# acdr_3_1.net
KiCad netlist of a schematic drawn in EAGLE
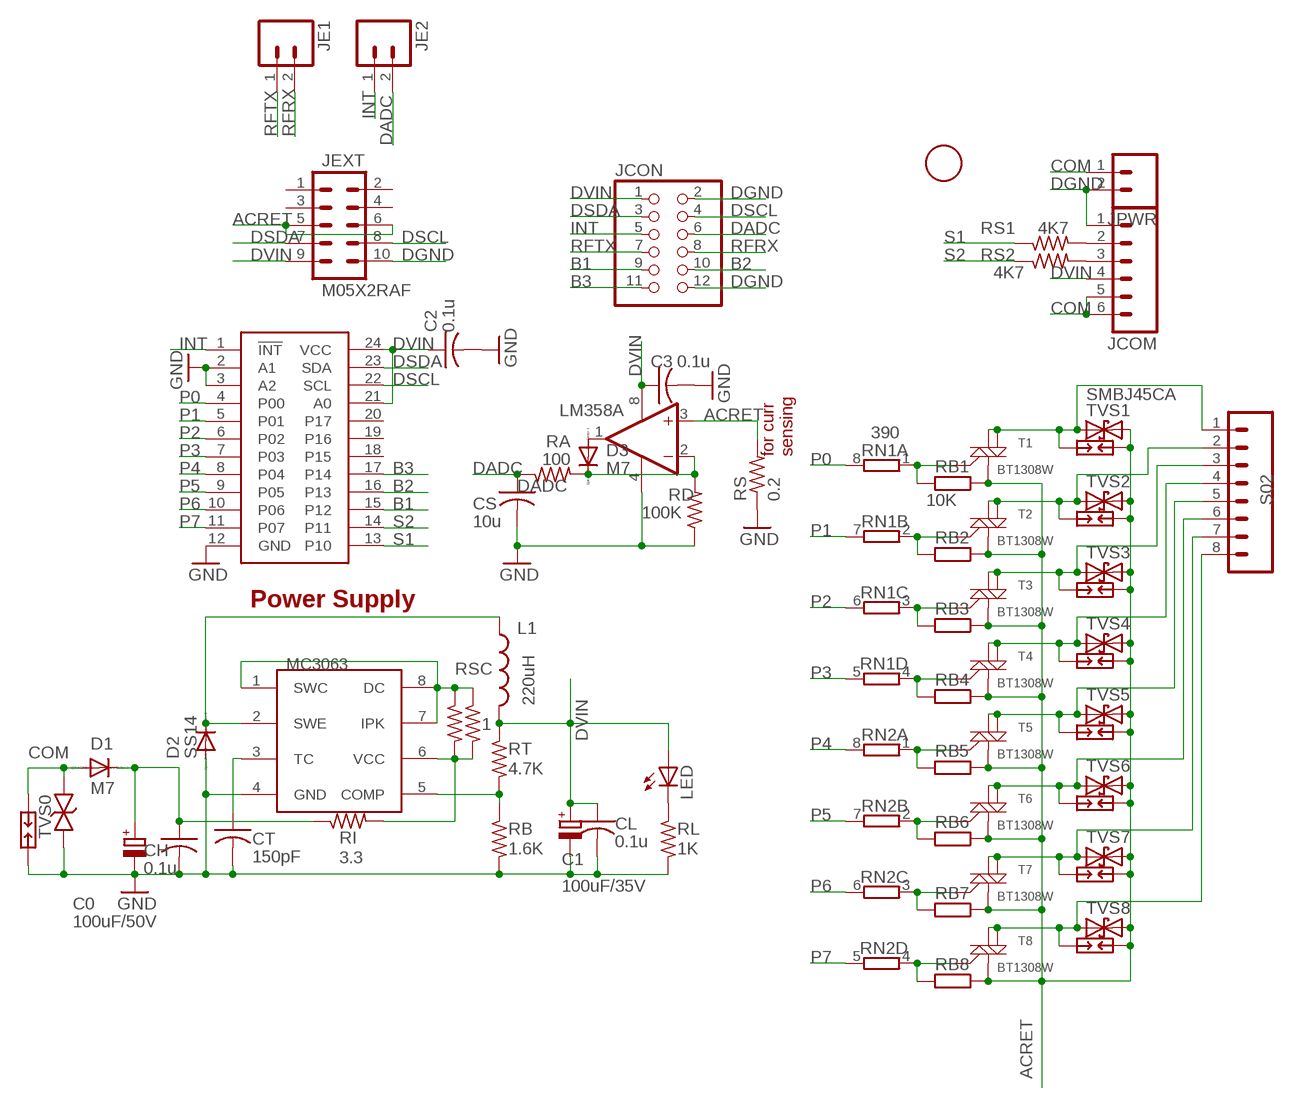
[diagram p0: schematic, sheet 1]

(export (version "E")
  (design (tool "Eeschema 10.0.6"))
  (components
    (comp (ref "1F")
      (value "FIDUCIAL")
      (footprint "eagle-import:FIDUCIAL_1MM")
      (libsource (lib "eagle-import") (part "FIDUCIAL"))
    )
    (comp (ref "C0")
      (value "100uF/50V")
      (footprint "eagle-import:PANASONIC_E")
      (libsource (lib "eagle-import") (part "CPOL-EUE"))
    )
    (comp (ref "C1")
      (value "100uF/35V")
      (footprint "eagle-import:PANASONIC_D")
      (libsource (lib "eagle-import") (part "CPOL-EUD"))
    )
    (comp (ref "C2")
      (value "0.1u")
      (footprint "eagle-import:C0603")
      (libsource (lib "eagle-import") (part "C-USC0603"))
    )
    (comp (ref "C3")
      (value "0.1u")
      (footprint "eagle-import:C0603")
      (libsource (lib "eagle-import") (part "C-USC0603"))
    )
    (comp (ref "CH")
      (value "0.1u")
      (footprint "eagle-import:C0603")
      (libsource (lib "eagle-import") (part "C-USC0603"))
    )
    (comp (ref "CL")
      (value "0.1u")
      (footprint "eagle-import:C0603")
      (libsource (lib "eagle-import") (part "C-USC0603"))
    )
    (comp (ref "CS")
      (value "10u")
      (footprint "eagle-import:C0805K")
      (libsource (lib "eagle-import") (part "C-USC0805K"))
    )
    (comp (ref "CT")
      (value "150pF")
      (footprint "eagle-import:C0603K")
      (libsource (lib "eagle-import") (part "C-USC0603K"))
    )
    (comp (ref "D1")
      (value "M7")
      (footprint "eagle-import:DO-214AC")
      (libsource (lib "eagle-import") (part "DIODE-DO-214AC"))
    )
    (comp (ref "D2")
      (value "SS14")
      (footprint "eagle-import:DO-214AC")
      (libsource (lib "eagle-import") (part "DIODE-DO-214AC"))
    )
    (comp (ref "D3")
      (value "M7")
      (footprint "eagle-import:DO-214AC")
      (libsource (lib "eagle-import") (part "DIODE-DO-214AC"))
    )
    (comp (ref "JCOM")
      (value "M065MM")
      (footprint "eagle-import:SCREWTERMINAL-5MM-6")
      (libsource (lib "eagle-import") (part "M065MM"))
    )
    (comp (ref "JCON")
      (value "PINHD-2X6")
      (footprint "eagle-import:2X06")
      (libsource (lib "eagle-import") (part "PINHD-2X6"))
    )
    (comp (ref "JE1")
      (value "M02PTH")
      (footprint "eagle-import:1X02")
      (libsource (lib "eagle-import") (part "SparkFunNew_M02PTH"))
    )
    (comp (ref "JE2")
      (value "M02PTH")
      (footprint "eagle-import:1X02")
      (libsource (lib "eagle-import") (part "SparkFunNew_M02PTH"))
    )
    (comp (ref "JEXT")
      (value "M05X2RAF")
      (footprint "eagle-import:2X5-RAF")
      (libsource (lib "eagle-import") (part "M05X2RAF"))
    )
    (comp (ref "JPWR")
      (value "M024MM-X")
      (footprint "eagle-import:SCREWTERMINAL-4MM-2-X")
      (libsource (lib "eagle-import") (part "M024MM-X"))
    )
    (comp (ref "L1")
      (value "220uH")
      (footprint "eagle-import:SRU1038")
      (libsource (lib "eagle-import") (part "INDUCTORSRU1038"))
    )
    (comp (ref "LED")
      (value "LEDCHIPLED_0805")
      (footprint "eagle-import:CHIPLED_0805")
      (libsource (lib "eagle-import") (part "LEDCHIPLED_0805"))
    )
    (comp (ref "LM358")
      (value "OP262D")
      (footprint "eagle-import:SO08")
      (libsource (lib "eagle-import") (part "OP262D"))
    )
    (comp (ref "MC3063")
      (value "MC34063")
      (footprint "eagle-import:SO08")
      (libsource (lib "eagle-import") (part "MC33063/MC34063D"))
    )
    (comp (ref "PCA9555")
      (value "PCA9555")
      (footprint "eagle-import:TSSOP24")
      (libsource (lib "eagle-import") (part "PCF8575TSSOP24"))
    )
    (comp (ref "RA")
      (value "100")
      (footprint "eagle-import:R0603")
      (libsource (lib "eagle-import") (part "R-US_R0603"))
    )
    (comp (ref "RB")
      (value "1.6K")
      (footprint "eagle-import:R0603")
      (libsource (lib "eagle-import") (part "adafruitGood_R-US_R0603"))
    )
    (comp (ref "RB1")
      (value "10K")
      (footprint "eagle-import:R0603")
      (libsource (lib "eagle-import") (part "R-EU_R0603"))
    )
    (comp (ref "RB2")
      (value "10K")
      (footprint "eagle-import:R0603")
      (libsource (lib "eagle-import") (part "R-EU_R0603"))
    )
    (comp (ref "RB3")
      (value "10K")
      (footprint "eagle-import:R0603")
      (libsource (lib "eagle-import") (part "R-EU_R0603"))
    )
    (comp (ref "RB4")
      (value "10K")
      (footprint "eagle-import:R0603")
      (libsource (lib "eagle-import") (part "R-EU_R0603"))
    )
    (comp (ref "RB5")
      (value "10K")
      (footprint "eagle-import:R0603")
      (libsource (lib "eagle-import") (part "R-EU_R0603"))
    )
    (comp (ref "RB6")
      (value "10K")
      (footprint "eagle-import:R0603")
      (libsource (lib "eagle-import") (part "R-EU_R0603"))
    )
    (comp (ref "RB7")
      (value "10K")
      (footprint "eagle-import:R0603")
      (libsource (lib "eagle-import") (part "R-EU_R0603"))
    )
    (comp (ref "RB8")
      (value "10K")
      (footprint "eagle-import:R0603")
      (libsource (lib "eagle-import") (part "R-EU_R0603"))
    )
    (comp (ref "RD")
      (value "100K")
      (footprint "eagle-import:R0603")
      (libsource (lib "eagle-import") (part "R-US_R0603"))
    )
    (comp (ref "RI")
      (value "3.3")
      (footprint "eagle-import:R2010")
      (libsource (lib "eagle-import") (part "adafruitGood_R-US_R2010"))
    )
    (comp (ref "RL")
      (value "1K")
      (footprint "eagle-import:R0603")
      (libsource (lib "eagle-import") (part "R-US_R0603"))
    )
    (comp (ref "RN1")
      (value "390")
      (footprint "eagle-import:EXB38V")
      (libsource (lib "eagle-import") (part "4R-NEXB38V"))
    )
    (comp (ref "RN2")
      (value "390")
      (footprint "eagle-import:EXB38V")
      (libsource (lib "eagle-import") (part "4R-NEXB38V"))
    )
    (comp (ref "RS")
      (value "0.2")
      (footprint "eagle-import:R2512")
      (libsource (lib "eagle-import") (part "R-US_R2512"))
    )
    (comp (ref "RS1")
      (value "4K7")
      (footprint "eagle-import:R0603")
      (libsource (lib "eagle-import") (part "R-US_R0603"))
    )
    (comp (ref "RS2")
      (value "4K7")
      (footprint "eagle-import:R0603")
      (libsource (lib "eagle-import") (part "R-US_R0603"))
    )
    (comp (ref "RSC")
      (value "1")
      (footprint "eagle-import:R0805")
      (libsource (lib "eagle-import") (part "adafruitGood_R-US_R0805"))
    )
    (comp (ref "RSC1")
      (value "1")
      (footprint "eagle-import:R0805")
      (libsource (lib "eagle-import") (part "adafruitGood_R-US_R0805"))
    )
    (comp (ref "RT")
      (value "4.7K")
      (footprint "eagle-import:R0603")
      (libsource (lib "eagle-import") (part "adafruitGood_R-US_R0603"))
    )
    (comp (ref "S02")
      (value "M085MM-8")
      (footprint "eagle-import:SCREWTERMINAL-5MM-8")
      (libsource (lib "eagle-import") (part "M085MM-8"))
    )
    (comp (ref "SP0")
      (value "PCB-SGAP")
      (footprint "eagle-import:PCB-SGAP")
      (libsource (lib "eagle-import") (part "PCB-SGAP"))
    )
    (comp (ref "SP1")
      (value "PCB-SGAP")
      (footprint "eagle-import:PCB-SGAP")
      (libsource (lib "eagle-import") (part "PCB-SGAP"))
    )
    (comp (ref "SP2")
      (value "PCB-SGAP")
      (footprint "eagle-import:PCB-SGAP")
      (libsource (lib "eagle-import") (part "PCB-SGAP"))
    )
    (comp (ref "SP3")
      (value "PCB-SGAP")
      (footprint "eagle-import:PCB-SGAP")
      (libsource (lib "eagle-import") (part "PCB-SGAP"))
    )
    (comp (ref "SP4")
      (value "PCB-SGAP")
      (footprint "eagle-import:PCB-SGAP")
      (libsource (lib "eagle-import") (part "PCB-SGAP"))
    )
    (comp (ref "SP5")
      (value "PCB-SGAP")
      (footprint "eagle-import:PCB-SGAP")
      (libsource (lib "eagle-import") (part "PCB-SGAP"))
    )
    (comp (ref "SP6")
      (value "PCB-SGAP")
      (footprint "eagle-import:PCB-SGAP")
      (libsource (lib "eagle-import") (part "PCB-SGAP"))
    )
    (comp (ref "SP7")
      (value "PCB-SGAP")
      (footprint "eagle-import:PCB-SGAP")
      (libsource (lib "eagle-import") (part "PCB-SGAP"))
    )
    (comp (ref "SP8")
      (value "PCB-SGAP")
      (footprint "eagle-import:PCB-SGAP")
      (libsource (lib "eagle-import") (part "PCB-SGAP"))
    )
    (comp (ref "T1")
      (value "BT1308W")
      (footprint "eagle-import:SOT223")
      (libsource (lib "eagle-import") (part "MAC97SOT223"))
    )
    (comp (ref "T2")
      (value "BT1308W")
      (footprint "eagle-import:SOT223")
      (libsource (lib "eagle-import") (part "MAC97SOT223"))
    )
    (comp (ref "T3")
      (value "BT1308W")
      (footprint "eagle-import:SOT223")
      (libsource (lib "eagle-import") (part "MAC97SOT223"))
    )
    (comp (ref "T4")
      (value "BT1308W")
      (footprint "eagle-import:SOT223")
      (libsource (lib "eagle-import") (part "MAC97SOT223"))
    )
    (comp (ref "T5")
      (value "BT1308W")
      (footprint "eagle-import:SOT223")
      (libsource (lib "eagle-import") (part "MAC97SOT223"))
    )
    (comp (ref "T6")
      (value "BT1308W")
      (footprint "eagle-import:SOT223")
      (libsource (lib "eagle-import") (part "MAC97SOT223"))
    )
    (comp (ref "T7")
      (value "BT1308W")
      (footprint "eagle-import:SOT223")
      (libsource (lib "eagle-import") (part "MAC97SOT223"))
    )
    (comp (ref "T8")
      (value "BT1308W")
      (footprint "eagle-import:SOT223")
      (libsource (lib "eagle-import") (part "MAC97SOT223"))
    )
    (comp (ref "TVS0")
      (value "SMBJ45CA")
      (footprint "eagle-import:SMB")
      (libsource (lib "eagle-import") (part "DIODE-BTVSSMB"))
    )
    (comp (ref "TVS1")
      (value "SMBJ45CA")
      (footprint "eagle-import:SMB")
      (libsource (lib "eagle-import") (part "TVSSMB"))
    )
    (comp (ref "TVS2")
      (value "SMBJ45CA")
      (footprint "eagle-import:SMB")
      (libsource (lib "eagle-import") (part "TVSSMB"))
    )
    (comp (ref "TVS3")
      (value "SMBJ45CA")
      (footprint "eagle-import:SMB")
      (libsource (lib "eagle-import") (part "TVSSMB"))
    )
    (comp (ref "TVS4")
      (value "SMBJ45CA")
      (footprint "eagle-import:SMB")
      (libsource (lib "eagle-import") (part "TVSSMB"))
    )
    (comp (ref "TVS5")
      (value "SMBJ45CA")
      (footprint "eagle-import:SMB")
      (libsource (lib "eagle-import") (part "TVSSMB"))
    )
    (comp (ref "TVS6")
      (value "SMBJ45CA")
      (footprint "eagle-import:SMB")
      (libsource (lib "eagle-import") (part "TVSSMB"))
    )
    (comp (ref "TVS7")
      (value "SMBJ45CA")
      (footprint "eagle-import:SMB")
      (libsource (lib "eagle-import") (part "TVSSMB"))
    )
    (comp (ref "TVS8")
      (value "SMBJ45CA")
      (footprint "eagle-import:SMB")
      (libsource (lib "eagle-import") (part "TVSSMB"))
    )
  )
  (nets
    (net (code "1") (name "/ACRET") (class "Default")
      (node (ref "JEXT") (pin "5") (pinfunction "5_5") (pintype "passive"))
      (node (ref "JEXT") (pin "6") (pinfunction "6_6") (pintype "passive"))
      (node (ref "LM358") (pin "3") (pinfunction "+IN_3") (pintype "input"))
      (node (ref "RB1") (pin "1") (pinfunction "1_1") (pintype "passive"))
      (node (ref "RB2") (pin "1") (pinfunction "1_1") (pintype "passive"))
      (node (ref "RB3") (pin "1") (pinfunction "1_1") (pintype "passive"))
      (node (ref "RB4") (pin "1") (pinfunction "1_1") (pintype "passive"))
      (node (ref "RB5") (pin "1") (pinfunction "1_1") (pintype "passive"))
      (node (ref "RB6") (pin "1") (pinfunction "1_1") (pintype "passive"))
      (node (ref "RB7") (pin "1") (pinfunction "1_1") (pintype "passive"))
      (node (ref "RB8") (pin "1") (pinfunction "1_1") (pintype "passive"))
      (node (ref "RS") (pin "2") (pinfunction "2_2") (pintype "passive"))
      (node (ref "SP1") (pin "1") (pinfunction "1_1") (pintype "passive"))
      (node (ref "SP2") (pin "1") (pinfunction "1_1") (pintype "passive"))
      (node (ref "SP3") (pin "1") (pinfunction "1_1") (pintype "passive"))
      (node (ref "SP4") (pin "1") (pinfunction "1_1") (pintype "passive"))
      (node (ref "SP5") (pin "1") (pinfunction "1_1") (pintype "passive"))
      (node (ref "SP6") (pin "1") (pinfunction "1_1") (pintype "passive"))
      (node (ref "SP7") (pin "1") (pinfunction "1_1") (pintype "passive"))
      (node (ref "SP8") (pin "1") (pinfunction "1_1") (pintype "passive"))
      (node (ref "T1") (pin "1") (pinfunction "M1_1") (pintype "bidirectional"))
      (node (ref "T2") (pin "1") (pinfunction "M1_1") (pintype "bidirectional"))
      (node (ref "T3") (pin "1") (pinfunction "M1_1") (pintype "bidirectional"))
      (node (ref "T4") (pin "1") (pinfunction "M1_1") (pintype "bidirectional"))
      (node (ref "T5") (pin "1") (pinfunction "M1_1") (pintype "bidirectional"))
      (node (ref "T6") (pin "1") (pinfunction "M1_1") (pintype "bidirectional"))
      (node (ref "T7") (pin "1") (pinfunction "M1_1") (pintype "bidirectional"))
      (node (ref "T8") (pin "1") (pinfunction "M1_1") (pintype "bidirectional"))
      (node (ref "TVS1") (pin "C") (pinfunction "C_C") (pintype "passive"))
      (node (ref "TVS2") (pin "C") (pinfunction "C_C") (pintype "passive"))
      (node (ref "TVS3") (pin "C") (pinfunction "C_C") (pintype "passive"))
      (node (ref "TVS4") (pin "C") (pinfunction "C_C") (pintype "passive"))
      (node (ref "TVS5") (pin "C") (pinfunction "C_C") (pintype "passive"))
      (node (ref "TVS6") (pin "C") (pinfunction "C_C") (pintype "passive"))
      (node (ref "TVS7") (pin "C") (pinfunction "C_C") (pintype "passive"))
      (node (ref "TVS8") (pin "C") (pinfunction "C_C") (pintype "passive"))
    )
    (net (code "2") (name "/B1") (class "Default")
      (node (ref "JCON") (pin "9") (pinfunction "9_9") (pintype "passive"))
      (node (ref "PCA9555") (pin "15") (pinfunction "P12_15") (pintype "bidirectional"))
    )
    (net (code "3") (name "/B2") (class "Default")
      (node (ref "JCON") (pin "10") (pinfunction "10_10") (pintype "passive"))
      (node (ref "PCA9555") (pin "16") (pinfunction "P13_16") (pintype "bidirectional"))
    )
    (net (code "4") (name "/B3") (class "Default")
      (node (ref "JCON") (pin "11") (pinfunction "11_11") (pintype "passive"))
      (node (ref "PCA9555") (pin "17") (pinfunction "P14_17") (pintype "bidirectional"))
    )
    (net (code "5") (name "/COM") (class "Default")
      (node (ref "D1") (pin "A") (pinfunction "A_A") (pintype "passive"))
      (node (ref "JCOM") (pin "5") (pinfunction "5_5") (pintype "passive"))
      (node (ref "JCOM") (pin "6") (pinfunction "6_6") (pintype "passive"))
      (node (ref "JPWR") (pin "1") (pinfunction "1_1") (pintype "passive"))
      (node (ref "SP0") (pin "1") (pinfunction "1_1") (pintype "passive"))
      (node (ref "TVS0") (pin "C") (pinfunction "C_C") (pintype "passive"))
    )
    (net (code "6") (name "/DADC") (class "Default")
      (node (ref "CS") (pin "1") (pinfunction "1_1") (pintype "passive"))
      (node (ref "JCON") (pin "6") (pinfunction "6_6") (pintype "passive"))
      (node (ref "JE2") (pin "2") (pinfunction "2_2") (pintype "passive"))
      (node (ref "RA") (pin "1") (pinfunction "1_1") (pintype "passive"))
    )
    (net (code "7") (name "/DSCL") (class "Default")
      (node (ref "JCON") (pin "4") (pinfunction "4_4") (pintype "passive"))
      (node (ref "JEXT") (pin "8") (pinfunction "8_8") (pintype "passive"))
      (node (ref "PCA9555") (pin "22") (pinfunction "SCL_22") (pintype "bidirectional"))
    )
    (net (code "8") (name "/DSDA") (class "Default")
      (node (ref "JCON") (pin "3") (pinfunction "3_3") (pintype "passive"))
      (node (ref "JEXT") (pin "7") (pinfunction "7_7") (pintype "passive"))
      (node (ref "PCA9555") (pin "23") (pinfunction "SDA_23") (pintype "bidirectional"))
    )
    (net (code "9") (name "/DVIN") (class "Default")
      (node (ref "C1") (pin "+") (pinfunction "+_+") (pintype "passive"))
      (node (ref "C2") (pin "1") (pinfunction "1_1") (pintype "passive"))
      (node (ref "C3") (pin "1") (pinfunction "1_1") (pintype "passive"))
      (node (ref "CL") (pin "1") (pinfunction "1_1") (pintype "passive"))
      (node (ref "JCOM") (pin "4") (pinfunction "4_4") (pintype "passive"))
      (node (ref "JCON") (pin "1") (pinfunction "1_1") (pintype "passive"))
      (node (ref "JEXT") (pin "9") (pinfunction "9_9") (pintype "passive"))
      (node (ref "L1") (pin "2") (pinfunction "2_2") (pintype "passive"))
      (node (ref "LED") (pin "A") (pinfunction "A_A") (pintype "passive"))
      (node (ref "LM358") (pin "8") (pinfunction "V+_8") (pintype "power_in"))
      (node (ref "PCA9555") (pin "21") (pinfunction "A0_21") (pintype "bidirectional"))
      (node (ref "PCA9555") (pin "24") (pinfunction "VCC_24") (pintype "power_in"))
      (node (ref "RT") (pin "1") (pinfunction "1_1") (pintype "passive"))
    )
    (net (code "10") (name "/INT") (class "Default")
      (node (ref "JCON") (pin "5") (pinfunction "5_5") (pintype "passive"))
      (node (ref "JE2") (pin "1") (pinfunction "1_1") (pintype "passive"))
      (node (ref "PCA9555") (pin "1") (pinfunction "~{INT}_1") (pintype "bidirectional"))
    )
    (net (code "11") (name "/P0") (class "Default")
      (node (ref "PCA9555") (pin "4") (pinfunction "P00_4") (pintype "bidirectional"))
      (node (ref "RN1") (pin "8") (pinfunction "2_8") (pintype "passive"))
    )
    (net (code "12") (name "/P1") (class "Default")
      (node (ref "PCA9555") (pin "5") (pinfunction "P01_5") (pintype "bidirectional"))
      (node (ref "RN1") (pin "7") (pinfunction "2_7") (pintype "passive"))
    )
    (net (code "13") (name "/P2") (class "Default")
      (node (ref "PCA9555") (pin "6") (pinfunction "P02_6") (pintype "bidirectional"))
      (node (ref "RN1") (pin "6") (pinfunction "2_6") (pintype "passive"))
    )
    (net (code "14") (name "/P3") (class "Default")
      (node (ref "PCA9555") (pin "7") (pinfunction "P03_7") (pintype "bidirectional"))
      (node (ref "RN1") (pin "5") (pinfunction "2_5") (pintype "passive"))
    )
    (net (code "15") (name "/P4") (class "Default")
      (node (ref "PCA9555") (pin "8") (pinfunction "P04_8") (pintype "bidirectional"))
      (node (ref "RN2") (pin "8") (pinfunction "2_8") (pintype "passive"))
    )
    (net (code "16") (name "/P5") (class "Default")
      (node (ref "PCA9555") (pin "9") (pinfunction "P05_9") (pintype "bidirectional"))
      (node (ref "RN2") (pin "7") (pinfunction "2_7") (pintype "passive"))
    )
    (net (code "17") (name "/P6") (class "Default")
      (node (ref "PCA9555") (pin "10") (pinfunction "P06_10") (pintype "bidirectional"))
      (node (ref "RN2") (pin "6") (pinfunction "2_6") (pintype "passive"))
    )
    (net (code "18") (name "/P7") (class "Default")
      (node (ref "PCA9555") (pin "11") (pinfunction "P07_11") (pintype "bidirectional"))
      (node (ref "RN2") (pin "5") (pinfunction "2_5") (pintype "passive"))
    )
    (net (code "19") (name "/RFRX") (class "Default")
      (node (ref "JCON") (pin "8") (pinfunction "8_8") (pintype "passive"))
      (node (ref "JE1") (pin "2") (pinfunction "2_2") (pintype "passive"))
    )
    (net (code "20") (name "/RFTX") (class "Default")
      (node (ref "JCON") (pin "7") (pinfunction "7_7") (pintype "passive"))
      (node (ref "JE1") (pin "1") (pinfunction "1_1") (pintype "passive"))
    )
    (net (code "21") (name "/S1") (class "Default")
      (node (ref "PCA9555") (pin "13") (pinfunction "P10_13") (pintype "bidirectional"))
      (node (ref "RS1") (pin "1") (pinfunction "1_1") (pintype "passive"))
    )
    (net (code "22") (name "/S2") (class "Default")
      (node (ref "PCA9555") (pin "14") (pinfunction "P11_14") (pintype "bidirectional"))
      (node (ref "RS2") (pin "1") (pinfunction "1_1") (pintype "passive"))
    )
    (net (code "23") (name "GND") (class "Default")
      (node (ref "C0") (pin "-") (pinfunction "-_-") (pintype "passive"))
      (node (ref "C1") (pin "-") (pinfunction "-_-") (pintype "passive"))
      (node (ref "C2") (pin "2") (pinfunction "2_2") (pintype "passive"))
      (node (ref "C3") (pin "2") (pinfunction "2_2") (pintype "passive"))
      (node (ref "CH") (pin "2") (pinfunction "2_2") (pintype "passive"))
      (node (ref "CL") (pin "2") (pinfunction "2_2") (pintype "passive"))
      (node (ref "CS") (pin "2") (pinfunction "2_2") (pintype "passive"))
      (node (ref "CT") (pin "2") (pinfunction "2_2") (pintype "passive"))
      (node (ref "D2") (pin "A") (pinfunction "A_A") (pintype "passive"))
      (node (ref "JCOM") (pin "1") (pinfunction "1_1") (pintype "passive"))
      (node (ref "JCON") (pin "12") (pinfunction "12_12") (pintype "passive"))
      (node (ref "JCON") (pin "2") (pinfunction "2_2") (pintype "passive"))
      (node (ref "JEXT") (pin "10") (pinfunction "10_10") (pintype "passive"))
      (node (ref "JPWR") (pin "2") (pinfunction "2_2") (pintype "passive"))
      (node (ref "LM358") (pin "4") (pinfunction "V-_4") (pintype "power_in"))
      (node (ref "MC3063") (pin "4") (pinfunction "GND_4") (pintype "power_in"))
      (node (ref "PCA9555") (pin "12") (pinfunction "GND_12") (pintype "power_in"))
      (node (ref "PCA9555") (pin "2") (pinfunction "A1_2") (pintype "bidirectional"))
      (node (ref "PCA9555") (pin "3") (pinfunction "A2_3") (pintype "bidirectional"))
      (node (ref "RB") (pin "2") (pinfunction "2_2") (pintype "passive"))
      (node (ref "RD") (pin "1") (pinfunction "1_1") (pintype "passive"))
      (node (ref "RL") (pin "2") (pinfunction "2_2") (pintype "passive"))
      (node (ref "RS") (pin "1") (pinfunction "1_1") (pintype "passive"))
      (node (ref "SP0") (pin "2") (pinfunction "2_2") (pintype "passive"))
      (node (ref "TVS0") (pin "A") (pinfunction "A_A") (pintype "passive"))
    )
    (net (code "24") (name "Net-(C0-Pad+)") (class "Default")
      (node (ref "C0") (pin "+") (pinfunction "+_+") (pintype "passive"))
      (node (ref "CH") (pin "1") (pinfunction "1_1") (pintype "passive"))
      (node (ref "D1") (pin "C") (pinfunction "C_C") (pintype "passive"))
      (node (ref "RI") (pin "1") (pinfunction "1_1") (pintype "passive"))
    )
    (net (code "25") (name "Net-(JCOM-Pad2)") (class "Default")
      (node (ref "JCOM") (pin "2") (pinfunction "2_2") (pintype "passive"))
      (node (ref "RS1") (pin "2") (pinfunction "2_2") (pintype "passive"))
    )
    (net (code "26") (name "Net-(JCOM-Pad3)") (class "Default")
      (node (ref "JCOM") (pin "3") (pinfunction "3_3") (pintype "passive"))
      (node (ref "RS2") (pin "2") (pinfunction "2_2") (pintype "passive"))
    )
    (net (code "27") (name "Net-(LED-PadC)") (class "Default")
      (node (ref "LED") (pin "C") (pinfunction "C_C") (pintype "passive"))
      (node (ref "RL") (pin "1") (pinfunction "1_1") (pintype "passive"))
    )
    (net (code "28") (name "Net-(LM358A--IN)") (class "Default")
      (node (ref "D3") (pin "C") (pinfunction "C_C") (pintype "passive"))
      (node (ref "LM358") (pin "2") (pinfunction "-IN_2") (pintype "input"))
      (node (ref "RA") (pin "2") (pinfunction "2_2") (pintype "passive"))
      (node (ref "RD") (pin "2") (pinfunction "2_2") (pintype "passive"))
    )
    (net (code "29") (name "Net-(LM358A-OUT)") (class "Default")
      (node (ref "D3") (pin "A") (pinfunction "A_A") (pintype "passive"))
      (node (ref "LM358") (pin "1") (pinfunction "OUT_1") (pintype "output"))
    )
    (net (code "30") (name "Net-(MC3063-COMP)") (class "Default")
      (node (ref "MC3063") (pin "5") (pinfunction "COMP_5") (pintype "input"))
      (node (ref "RB") (pin "1") (pinfunction "1_1") (pintype "passive"))
      (node (ref "RT") (pin "2") (pinfunction "2_2") (pintype "passive"))
    )
    (net (code "31") (name "Net-(MC3063-DC)") (class "Default")
      (node (ref "MC3063") (pin "1") (pinfunction "SWC_1") (pintype "input"))
      (node (ref "MC3063") (pin "7") (pinfunction "IPK_7") (pintype "bidirectional"))
      (node (ref "MC3063") (pin "8") (pinfunction "DC_8") (pintype "input"))
      (node (ref "RSC") (pin "1") (pinfunction "1_1") (pintype "passive"))
      (node (ref "RSC1") (pin "1") (pinfunction "1_1") (pintype "passive"))
    )
    (net (code "32") (name "Net-(MC3063-SWE)") (class "Default")
      (node (ref "D2") (pin "C") (pinfunction "C_C") (pintype "passive"))
      (node (ref "L1") (pin "1") (pinfunction "1_1") (pintype "passive"))
      (node (ref "MC3063") (pin "2") (pinfunction "SWE_2") (pintype "input"))
    )
    (net (code "33") (name "Net-(MC3063-TC)") (class "Default")
      (node (ref "CT") (pin "1") (pinfunction "1_1") (pintype "passive"))
      (node (ref "MC3063") (pin "3") (pinfunction "TC_3") (pintype "input"))
    )
    (net (code "34") (name "Net-(MC3063-VCC)") (class "Default")
      (node (ref "MC3063") (pin "6") (pinfunction "VCC_6") (pintype "power_in"))
      (node (ref "RI") (pin "2") (pinfunction "2_2") (pintype "passive"))
      (node (ref "RSC") (pin "2") (pinfunction "2_2") (pintype "passive"))
      (node (ref "RSC1") (pin "2") (pinfunction "2_2") (pintype "passive"))
    )
    (net (code "35") (name "Net-(RN1B-1)") (class "Default")
      (node (ref "RB2") (pin "2") (pinfunction "2_2") (pintype "passive"))
      (node (ref "RN1") (pin "2") (pinfunction "1_2") (pintype "passive"))
      (node (ref "T2") (pin "3") (pinfunction "G_3") (pintype "bidirectional"))
    )
    (net (code "36") (name "Net-(RN1C-1)") (class "Default")
      (node (ref "RB3") (pin "2") (pinfunction "2_2") (pintype "passive"))
      (node (ref "RN1") (pin "3") (pinfunction "1_3") (pintype "passive"))
      (node (ref "T3") (pin "3") (pinfunction "G_3") (pintype "bidirectional"))
    )
    (net (code "37") (name "Net-(RN1D-1)") (class "Default")
      (node (ref "RB4") (pin "2") (pinfunction "2_2") (pintype "passive"))
      (node (ref "RN1") (pin "4") (pinfunction "1_4") (pintype "passive"))
      (node (ref "T4") (pin "3") (pinfunction "G_3") (pintype "bidirectional"))
    )
    (net (code "38") (name "Net-(RN2B-1)") (class "Default")
      (node (ref "RB6") (pin "2") (pinfunction "2_2") (pintype "passive"))
      (node (ref "RN2") (pin "2") (pinfunction "1_2") (pintype "passive"))
      (node (ref "T6") (pin "3") (pinfunction "G_3") (pintype "bidirectional"))
    )
    (net (code "39") (name "Net-(RN2C-1)") (class "Default")
      (node (ref "RB7") (pin "2") (pinfunction "2_2") (pintype "passive"))
      (node (ref "RN2") (pin "3") (pinfunction "1_3") (pintype "passive"))
      (node (ref "T7") (pin "3") (pinfunction "G_3") (pintype "bidirectional"))
    )
    (net (code "40") (name "Net-(RN2D-1)") (class "Default")
      (node (ref "RB8") (pin "2") (pinfunction "2_2") (pintype "passive"))
      (node (ref "RN2") (pin "4") (pinfunction "1_4") (pintype "passive"))
      (node (ref "T8") (pin "3") (pinfunction "G_3") (pintype "bidirectional"))
    )
    (net (code "41") (name "Net-(T1-G)") (class "Default")
      (node (ref "RB1") (pin "2") (pinfunction "2_2") (pintype "passive"))
      (node (ref "RN1") (pin "1") (pinfunction "1_1") (pintype "passive"))
      (node (ref "T1") (pin "3") (pinfunction "G_3") (pintype "bidirectional"))
    )
    (net (code "42") (name "Net-(T1-M2)") (class "Default")
      (node (ref "S02") (pin "1") (pinfunction "1_1") (pintype "passive"))
      (node (ref "SP1") (pin "2") (pinfunction "2_2") (pintype "passive"))
      (node (ref "T1") (pin "2") (pinfunction "M2_2") (pintype "bidirectional"))
      (node (ref "T1") (pin "4") (pinfunction "M2-4_4") (pintype "bidirectional"))
      (node (ref "TVS1") (pin "A") (pinfunction "A_A") (pintype "passive"))
    )
    (net (code "43") (name "Net-(T2-M2)") (class "Default")
      (node (ref "S02") (pin "2") (pinfunction "2_2") (pintype "passive"))
      (node (ref "SP2") (pin "2") (pinfunction "2_2") (pintype "passive"))
      (node (ref "T2") (pin "2") (pinfunction "M2_2") (pintype "bidirectional"))
      (node (ref "T2") (pin "4") (pinfunction "M2-4_4") (pintype "bidirectional"))
      (node (ref "TVS2") (pin "A") (pinfunction "A_A") (pintype "passive"))
    )
    (net (code "44") (name "Net-(T3-M2)") (class "Default")
      (node (ref "S02") (pin "3") (pinfunction "3_3") (pintype "passive"))
      (node (ref "SP3") (pin "2") (pinfunction "2_2") (pintype "passive"))
      (node (ref "T3") (pin "2") (pinfunction "M2_2") (pintype "bidirectional"))
      (node (ref "T3") (pin "4") (pinfunction "M2-4_4") (pintype "bidirectional"))
      (node (ref "TVS3") (pin "A") (pinfunction "A_A") (pintype "passive"))
    )
    (net (code "45") (name "Net-(T4-M2)") (class "Default")
      (node (ref "S02") (pin "4") (pinfunction "4_4") (pintype "passive"))
      (node (ref "SP4") (pin "2") (pinfunction "2_2") (pintype "passive"))
      (node (ref "T4") (pin "2") (pinfunction "M2_2") (pintype "bidirectional"))
      (node (ref "T4") (pin "4") (pinfunction "M2-4_4") (pintype "bidirectional"))
      (node (ref "TVS4") (pin "A") (pinfunction "A_A") (pintype "passive"))
    )
    (net (code "46") (name "Net-(T5-G)") (class "Default")
      (node (ref "RB5") (pin "2") (pinfunction "2_2") (pintype "passive"))
      (node (ref "RN2") (pin "1") (pinfunction "1_1") (pintype "passive"))
      (node (ref "T5") (pin "3") (pinfunction "G_3") (pintype "bidirectional"))
    )
    (net (code "47") (name "Net-(T5-M2)") (class "Default")
      (node (ref "S02") (pin "5") (pinfunction "5_5") (pintype "passive"))
      (node (ref "SP5") (pin "2") (pinfunction "2_2") (pintype "passive"))
      (node (ref "T5") (pin "2") (pinfunction "M2_2") (pintype "bidirectional"))
      (node (ref "T5") (pin "4") (pinfunction "M2-4_4") (pintype "bidirectional"))
      (node (ref "TVS5") (pin "A") (pinfunction "A_A") (pintype "passive"))
    )
    (net (code "48") (name "Net-(T6-M2)") (class "Default")
      (node (ref "S02") (pin "6") (pinfunction "6_6") (pintype "passive"))
      (node (ref "SP6") (pin "2") (pinfunction "2_2") (pintype "passive"))
      (node (ref "T6") (pin "2") (pinfunction "M2_2") (pintype "bidirectional"))
      (node (ref "T6") (pin "4") (pinfunction "M2-4_4") (pintype "bidirectional"))
      (node (ref "TVS6") (pin "A") (pinfunction "A_A") (pintype "passive"))
    )
    (net (code "49") (name "Net-(T7-M2)") (class "Default")
      (node (ref "S02") (pin "7") (pinfunction "7_7") (pintype "passive"))
      (node (ref "SP7") (pin "2") (pinfunction "2_2") (pintype "passive"))
      (node (ref "T7") (pin "2") (pinfunction "M2_2") (pintype "bidirectional"))
      (node (ref "T7") (pin "4") (pinfunction "M2-4_4") (pintype "bidirectional"))
      (node (ref "TVS7") (pin "A") (pinfunction "A_A") (pintype "passive"))
    )
    (net (code "50") (name "Net-(T8-M2)") (class "Default")
      (node (ref "S02") (pin "8") (pinfunction "8_8") (pintype "passive"))
      (node (ref "SP8") (pin "2") (pinfunction "2_2") (pintype "passive"))
      (node (ref "T8") (pin "2") (pinfunction "M2_2") (pintype "bidirectional"))
      (node (ref "T8") (pin "4") (pinfunction "M2-4_4") (pintype "bidirectional"))
      (node (ref "TVS8") (pin "A") (pinfunction "A_A") (pintype "passive"))
    )
    (net (code "51") (name "unconnected-(JEXT-Pad1)") (class "Default")
      (node (ref "JEXT") (pin "1") (pinfunction "1_1") (pintype "passive"))
    )
    (net (code "52") (name "unconnected-(JEXT-Pad2)") (class "Default")
      (node (ref "JEXT") (pin "2") (pinfunction "2_2") (pintype "passive"))
    )
    (net (code "53") (name "unconnected-(JEXT-Pad3)") (class "Default")
      (node (ref "JEXT") (pin "3") (pinfunction "3_3") (pintype "passive"))
    )
    (net (code "54") (name "unconnected-(JEXT-Pad4)") (class "Default")
      (node (ref "JEXT") (pin "4") (pinfunction "4_4") (pintype "passive"))
    )
    (net (code "55") (name "unconnected-(PCA9555-P15-Pad18)") (class "Default")
      (node (ref "PCA9555") (pin "18") (pinfunction "P15_18") (pintype "bidirectional"))
    )
    (net (code "56") (name "unconnected-(PCA9555-P16-Pad19)") (class "Default")
      (node (ref "PCA9555") (pin "19") (pinfunction "P16_19") (pintype "bidirectional"))
    )
    (net (code "57") (name "unconnected-(PCA9555-P17-Pad20)") (class "Default")
      (node (ref "PCA9555") (pin "20") (pinfunction "P17_20") (pintype "bidirectional"))
    )
  )
)
